# PDM-S01-V00-IsolatedCAN.net
KiCad netlist of a schematic drawn in Altium Designer
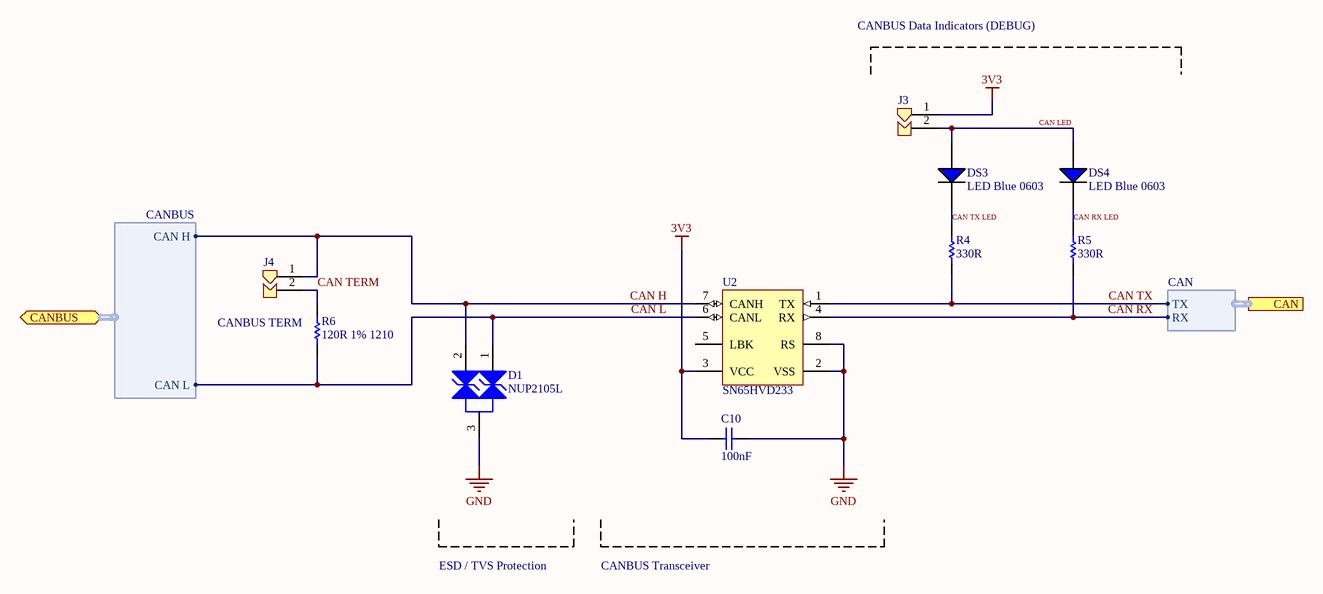
[diagram p0: PDM-S01-V00-IsolatedCAN.SchDoc]

(export (version "E")
  (design (tool "Eeschema 10.0.6"))
  (components
    (comp (ref "C10")
      (value "100nF")
      (footprint "Cap_Ceramic_0603")
      (description "Capacitor, Ceramic, SMD, 100nF, 50V, 5%, X7R, 0603")
      (libsource (lib "StandardCapacitors") (part "100nF 50V 5% X7R 0603"))
    )
    (comp (ref "D1")
      (value "NUP2105L")
      (footprint "NUP2105L")
      (libsource (lib "QUTMS_CANLibrary") (part "NUP2105L"))
    )
    (comp (ref "DS3")
      (value "LED Blue 0603")
      (footprint "LED BLUE 0603")
      (libsource (lib "QUTMS_LEDLibrary") (part "LED BLUE 0603"))
    )
    (comp (ref "DS4")
      (value "LED Blue 0603")
      (footprint "LED BLUE 0603")
      (libsource (lib "QUTMS_LEDLibrary") (part "LED BLUE 0603"))
    )
    (comp (ref "J3")
      (value "Jumper 2Way Solderable")
      (footprint "Jumper_2Way_Solderable")
      (description "Jumper 2Way Side Solderable")
      (libsource (lib "QUTMS_JumperLibrary") (part "Jumper 2Way Side Solderable"))
    )
    (comp (ref "J4")
      (value "Jumper 2Way Solderable")
      (footprint "Jumper_2Way_Solderable")
      (description "Jumper 2Way Side Solderable")
      (libsource (lib "QUTMS_JumperLibrary") (part "Jumper 2Way Side Solderable"))
    )
    (comp (ref "R4")
      (value "330R")
      (footprint "Res_ThinFilm_0603")
      (description "Resistor, SMD, 330R, 0.1W, 5%, 0603")
      (libsource (lib "StandardResistors") (part "330R 5% 0603"))
    )
    (comp (ref "R5")
      (value "330R")
      (footprint "Res_ThinFilm_0603")
      (description "Resistor, SMD, 330R, 0.1W, 5%, 0603")
      (libsource (lib "StandardResistors") (part "330R 5% 0603"))
    )
    (comp (ref "R6")
      (value "120R 1% 1210")
      (footprint "Res_ThinFilm_1210")
      (description "Resistor, SMD, 120R, 0.25W, 1%, 1210")
      (libsource (lib "StandardResistors") (part "120R 1% 1210"))
    )
    (comp (ref "U2")
      (value "SN65HVD233")
      (footprint "SN65HVD233DR")
      (libsource (lib "QUTMS_CANLibrary") (part "SN65HVD233"))
    )
  )
  (nets
    (net (code "3") (name "/CAN H") (class "Default")
      (node (ref "D1") (pin "2") (pinfunction "2_2") (pintype "passive"))
      (node (ref "J4") (pin "1") (pinfunction "1_1") (pintype "passive"))
      (node (ref "U2") (pin "7") (pinfunction "CANH_7") (pintype "bidirectional"))
    )
    (net (code "4") (name "/CAN L") (class "Default")
      (node (ref "D1") (pin "1") (pinfunction "1_1") (pintype "passive"))
      (node (ref "R6") (pin "1") (pinfunction "1_1") (pintype "passive"))
      (node (ref "U2") (pin "6") (pinfunction "CANL_6") (pintype "bidirectional"))
    )
    (net (code "5") (name "/CAN LED") (class "Default")
      (node (ref "DS3") (pin "1") (pinfunction "A_1") (pintype "passive"))
      (node (ref "DS4") (pin "1") (pinfunction "A_1") (pintype "passive"))
      (node (ref "J3") (pin "2") (pinfunction "2_2") (pintype "passive"))
    )
    (net (code "6") (name "/CAN RX") (class "Default")
      (node (ref "R5") (pin "1") (pinfunction "1_1") (pintype "passive"))
      (node (ref "U2") (pin "4") (pinfunction "RX_4") (pintype "output"))
    )
    (net (code "7") (name "/CAN RX LED") (class "Default")
      (node (ref "DS4") (pin "2") (pinfunction "C_2") (pintype "passive"))
      (node (ref "R5") (pin "2") (pinfunction "2_2") (pintype "passive"))
    )
    (net (code "8") (name "/CAN TERM") (class "Default")
      (node (ref "J4") (pin "2") (pinfunction "2_2") (pintype "passive"))
      (node (ref "R6") (pin "2") (pinfunction "2_2") (pintype "passive"))
    )
    (net (code "9") (name "/CAN TX") (class "Default")
      (node (ref "R4") (pin "1") (pinfunction "1_1") (pintype "passive"))
      (node (ref "U2") (pin "1") (pinfunction "TX_1") (pintype "input"))
    )
    (net (code "10") (name "/CAN TX LED") (class "Default")
      (node (ref "DS3") (pin "2") (pinfunction "C_2") (pintype "passive"))
      (node (ref "R4") (pin "2") (pinfunction "2_2") (pintype "passive"))
    )
    (net (code "13") (name "3V3") (class "Default")
      (node (ref "C10") (pin "2") (pinfunction "2_2") (pintype "passive"))
      (node (ref "J3") (pin "1") (pinfunction "1_1") (pintype "passive"))
      (node (ref "U2") (pin "3") (pinfunction "VCC_3") (pintype "passive"))
    )
    (net (code "14") (name "GND") (class "Default")
      (node (ref "C10") (pin "1") (pinfunction "1_1") (pintype "passive"))
      (node (ref "D1") (pin "3") (pinfunction "3_3") (pintype "passive"))
      (node (ref "U2") (pin "2") (pinfunction "VSS_2") (pintype "passive"))
      (node (ref "U2") (pin "8") (pinfunction "RS_8") (pintype "passive"))
    )
    (net (code "15") (name "unconnected-(U2-LBK-Pad5)") (class "Default")
      (node (ref "U2") (pin "5") (pinfunction "LBK_5") (pintype "passive"))
    )
  )
)
